# NixieClock.net
KiCad netlist of a schematic drawn in EAGLE
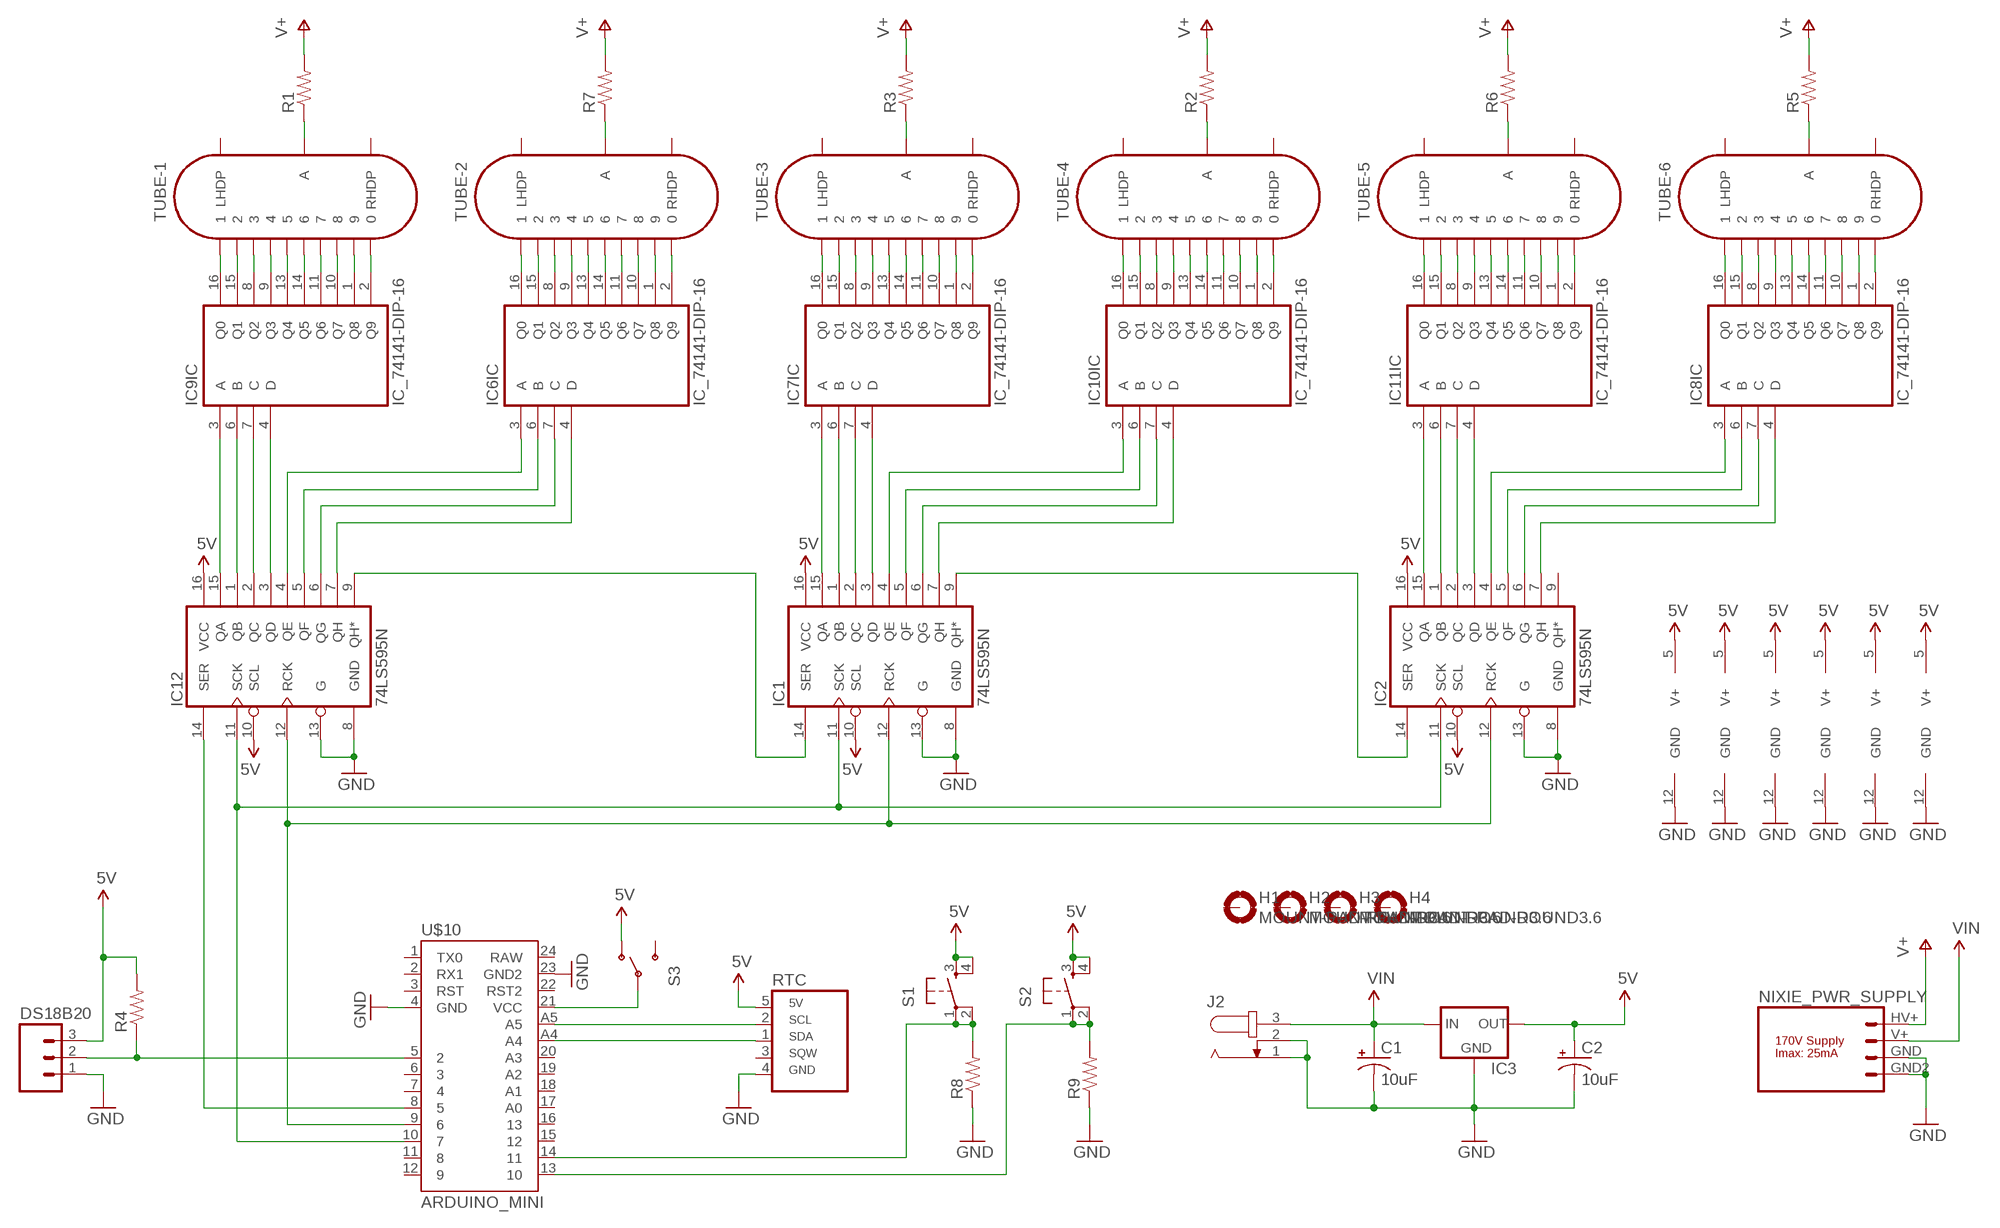
[diagram p0: schematic, sheet 1]

(export (version "E")
  (design (tool "Eeschema 10.0.6"))
  (components
    (comp (ref "C1")
      (value "10uF")
      (footprint "eagle-import:CPOL-RADIAL-10UF-25V")
      (libsource (lib "eagle-import") (part "CAP_POLPTH2"))
    )
    (comp (ref "C2")
      (value "10uF")
      (footprint "eagle-import:CPOL-RADIAL-10UF-25V")
      (libsource (lib "eagle-import") (part "CAP_POLPTH2"))
    )
    (comp (ref "DS18B20")
      (value "DS18B20DS18B20")
      (footprint "eagle-import:DS18B20")
      (libsource (lib "eagle-import") (part "DS18B20DS18B20"))
    )
    (comp (ref "H1")
      (value "MOUNT-PAD-ROUND3.6")
      (footprint "eagle-import:3,6-PAD")
      (libsource (lib "eagle-import") (part "MOUNT-PAD-ROUND3.6"))
    )
    (comp (ref "H2")
      (value "MOUNT-PAD-ROUND3.6")
      (footprint "eagle-import:3,6-PAD")
      (libsource (lib "eagle-import") (part "MOUNT-PAD-ROUND3.6"))
    )
    (comp (ref "H3")
      (value "MOUNT-PAD-ROUND3.6")
      (footprint "eagle-import:3,6-PAD")
      (libsource (lib "eagle-import") (part "MOUNT-PAD-ROUND3.6"))
    )
    (comp (ref "H4")
      (value "MOUNT-PAD-ROUND3.6")
      (footprint "eagle-import:3,6-PAD")
      (libsource (lib "eagle-import") (part "MOUNT-PAD-ROUND3.6"))
    )
    (comp (ref "IC1")
      (value "74LS595N")
      (footprint "eagle-import:DIL16")
      (libsource (lib "eagle-import") (part "74595NLS"))
    )
    (comp (ref "IC2")
      (value "74LS595N")
      (footprint "eagle-import:DIL16")
      (libsource (lib "eagle-import") (part "74595NLS"))
    )
    (comp (ref "IC3")
      (value "V_REG_78XXSIDE")
      (footprint "eagle-import:78XXL")
      (libsource (lib "eagle-import") (part "V_REG_78XXSIDE"))
    )
    (comp (ref "IC6")
      (value "IC_74141-DIP-16")
      (footprint "eagle-import:DIL16")
      (libsource (lib "eagle-import") (part "IC_74141-DIP-16"))
    )
    (comp (ref "IC7")
      (value "IC_74141-DIP-16")
      (footprint "eagle-import:DIL16")
      (libsource (lib "eagle-import") (part "IC_74141-DIP-16"))
    )
    (comp (ref "IC8")
      (value "IC_74141-DIP-16")
      (footprint "eagle-import:DIL16")
      (libsource (lib "eagle-import") (part "IC_74141-DIP-16"))
    )
    (comp (ref "IC9")
      (value "IC_74141-DIP-16")
      (footprint "eagle-import:DIL16")
      (libsource (lib "eagle-import") (part "IC_74141-DIP-16"))
    )
    (comp (ref "IC10")
      (value "IC_74141-DIP-16")
      (footprint "eagle-import:DIL16")
      (libsource (lib "eagle-import") (part "IC_74141-DIP-16"))
    )
    (comp (ref "IC11")
      (value "IC_74141-DIP-16")
      (footprint "eagle-import:DIL16")
      (libsource (lib "eagle-import") (part "IC_74141-DIP-16"))
    )
    (comp (ref "IC12")
      (value "74LS595N")
      (footprint "eagle-import:DIL16")
      (libsource (lib "eagle-import") (part "74595NLS"))
    )
    (comp (ref "J2")
      (value "JACK-PLUG0")
      (footprint "eagle-import:SPC4077")
      (libsource (lib "eagle-import") (part "JACK-PLUG0"))
    )
    (comp (ref "NIXIE_PWR_SUPPLY")
      (value "NIXIE_PWR_SUPPLYPTH")
      (footprint "eagle-import:NIXIE_PWR_SUPPLY")
      (libsource (lib "eagle-import") (part "NIXIE_PWR_SUPPLYPTH"))
    )
    (comp (ref "R1")
      (value "RESISTORPTH-1/4W")
      (footprint "eagle-import:AXIAL-0.4")
      (libsource (lib "eagle-import") (part "RESISTORPTH-1/4W"))
    )
    (comp (ref "R2")
      (value "RESISTORPTH-1/4W")
      (footprint "eagle-import:AXIAL-0.4")
      (libsource (lib "eagle-import") (part "RESISTORPTH-1/4W"))
    )
    (comp (ref "R3")
      (value "RESISTORPTH-1/4W")
      (footprint "eagle-import:AXIAL-0.4")
      (libsource (lib "eagle-import") (part "RESISTORPTH-1/4W"))
    )
    (comp (ref "R4")
      (value "RESISTORPTH-1/4W")
      (footprint "eagle-import:AXIAL-0.4")
      (libsource (lib "eagle-import") (part "SparkFun-Passives_RESISTORPTH-1/4W"))
    )
    (comp (ref "R5")
      (value "RESISTORPTH-1/4W")
      (footprint "eagle-import:AXIAL-0.4")
      (libsource (lib "eagle-import") (part "RESISTORPTH-1/4W"))
    )
    (comp (ref "R6")
      (value "RESISTORPTH-1/4W")
      (footprint "eagle-import:AXIAL-0.4")
      (libsource (lib "eagle-import") (part "RESISTORPTH-1/4W"))
    )
    (comp (ref "R7")
      (value "RESISTORPTH-1/4W")
      (footprint "eagle-import:AXIAL-0.4")
      (libsource (lib "eagle-import") (part "RESISTORPTH-1/4W"))
    )
    (comp (ref "R8")
      (value "RESISTORPTH-1/4W")
      (footprint "eagle-import:AXIAL-0.4")
      (libsource (lib "eagle-import") (part "SparkFun-Passives_RESISTORPTH-1/4W"))
    )
    (comp (ref "R9")
      (value "RESISTORPTH-1/4W")
      (footprint "eagle-import:AXIAL-0.4")
      (libsource (lib "eagle-import") (part "SparkFun-Passives_RESISTORPTH-1/4W"))
    )
    (comp (ref "RTC")
      (value "SCOTT_RTCPTH")
      (footprint "eagle-import:SCOTT_RTC")
      (libsource (lib "eagle-import") (part "SCOTT_RTCPTH"))
    )
    (comp (ref "S1")
      (value "TAC_SWITCHPTH")
      (footprint "eagle-import:TACTILE-PTH")
      (libsource (lib "eagle-import") (part "TAC_SWITCHPTH"))
    )
    (comp (ref "S2")
      (value "TAC_SWITCHPTH")
      (footprint "eagle-import:TACTILE-PTH")
      (libsource (lib "eagle-import") (part "TAC_SWITCHPTH"))
    )
    (comp (ref "S3")
      (value "SWITCH-SPDTPTH")
      (footprint "eagle-import:SWITCH-SPDT")
      (libsource (lib "eagle-import") (part "SWITCH-SPDTPTH"))
    )
    (comp (ref "TUBE-1")
      (value "IN-14")
      (footprint "eagle-import:IN-14")
      (libsource (lib "eagle-import") (part "IN-14"))
    )
    (comp (ref "TUBE-2")
      (value "IN-14")
      (footprint "eagle-import:IN-14")
      (libsource (lib "eagle-import") (part "IN-14"))
    )
    (comp (ref "TUBE-3")
      (value "IN-14")
      (footprint "eagle-import:IN-14")
      (libsource (lib "eagle-import") (part "IN-14"))
    )
    (comp (ref "TUBE-4")
      (value "IN-14")
      (footprint "eagle-import:IN-14")
      (libsource (lib "eagle-import") (part "IN-14"))
    )
    (comp (ref "TUBE-5")
      (value "IN-14")
      (footprint "eagle-import:IN-14")
      (libsource (lib "eagle-import") (part "IN-14"))
    )
    (comp (ref "TUBE-6")
      (value "IN-14")
      (footprint "eagle-import:IN-14")
      (libsource (lib "eagle-import") (part "IN-14"))
    )
    (comp (ref "U$10")
      (value "ARDUINO_MINI")
      (footprint "eagle-import:ARDUINO_MINI")
      (libsource (lib "eagle-import") (part "ARDUINO_MINI"))
    )
  )
  (nets
    (net (code "1") (name "5V") (class "Default")
      (node (ref "C2") (pin "1") (pinfunction "+_1") (pintype "passive"))
      (node (ref "DS18B20") (pin "3") (pinfunction "5V_3") (pintype "passive"))
      (node (ref "IC1") (pin "10") (pinfunction "SCL_10") (pintype "input"))
      (node (ref "IC1") (pin "16") (pinfunction "VCC_16") (pintype "power_in"))
      (node (ref "IC10") (pin "5") (pinfunction "V+_5") (pintype "power_in"))
      (node (ref "IC11") (pin "5") (pinfunction "V+_5") (pintype "power_in"))
      (node (ref "IC12") (pin "10") (pinfunction "SCL_10") (pintype "input"))
      (node (ref "IC12") (pin "16") (pinfunction "VCC_16") (pintype "power_in"))
      (node (ref "IC2") (pin "10") (pinfunction "SCL_10") (pintype "input"))
      (node (ref "IC2") (pin "16") (pinfunction "VCC_16") (pintype "power_in"))
      (node (ref "IC3") (pin "OUT") (pinfunction "OUT_OUT") (pintype "output"))
      (node (ref "IC6") (pin "5") (pinfunction "V+_5") (pintype "power_in"))
      (node (ref "IC7") (pin "5") (pinfunction "V+_5") (pintype "power_in"))
      (node (ref "IC8") (pin "5") (pinfunction "V+_5") (pintype "power_in"))
      (node (ref "IC9") (pin "5") (pinfunction "V+_5") (pintype "power_in"))
      (node (ref "R4") (pin "P$2") (pinfunction "2_P$2") (pintype "passive"))
      (node (ref "RTC") (pin "5") (pinfunction "5V_5") (pintype "passive"))
      (node (ref "S1") (pin "3") (pinfunction "3_3") (pintype "passive"))
      (node (ref "S1") (pin "4") (pinfunction "4_4") (pintype "passive"))
      (node (ref "S2") (pin "3") (pinfunction "3_3") (pintype "passive"))
      (node (ref "S2") (pin "4") (pinfunction "4_4") (pintype "passive"))
      (node (ref "S3") (pin "1") (pinfunction "O_1") (pintype "passive"))
    )
    (net (code "2") (name "GND") (class "Default")
      (node (ref "C1") (pin "2") (pinfunction "-_2") (pintype "passive"))
      (node (ref "C2") (pin "2") (pinfunction "-_2") (pintype "passive"))
      (node (ref "DS18B20") (pin "1") (pinfunction "GND_1") (pintype "passive"))
      (node (ref "IC1") (pin "13") (pinfunction "G_13") (pintype "input"))
      (node (ref "IC1") (pin "8") (pinfunction "GND_8") (pintype "power_in"))
      (node (ref "IC10") (pin "12") (pinfunction "GND_12") (pintype "power_in"))
      (node (ref "IC11") (pin "12") (pinfunction "GND_12") (pintype "power_in"))
      (node (ref "IC12") (pin "13") (pinfunction "G_13") (pintype "input"))
      (node (ref "IC12") (pin "8") (pinfunction "GND_8") (pintype "power_in"))
      (node (ref "IC2") (pin "13") (pinfunction "G_13") (pintype "input"))
      (node (ref "IC2") (pin "8") (pinfunction "GND_8") (pintype "power_in"))
      (node (ref "IC3") (pin "GND") (pinfunction "GND_GND") (pintype "input"))
      (node (ref "IC6") (pin "12") (pinfunction "GND_12") (pintype "power_in"))
      (node (ref "IC7") (pin "12") (pinfunction "GND_12") (pintype "power_in"))
      (node (ref "IC8") (pin "12") (pinfunction "GND_12") (pintype "power_in"))
      (node (ref "IC9") (pin "12") (pinfunction "GND_12") (pintype "power_in"))
      (node (ref "J2") (pin "1") (pinfunction "1_1") (pintype "passive"))
      (node (ref "J2") (pin "2") (pinfunction "2_2") (pintype "passive"))
      (node (ref "NIXIE_PWR_SUPPLY") (pin "GND") (pinfunction "4_GND") (pintype "passive"))
      (node (ref "NIXIE_PWR_SUPPLY") (pin "GND2") (pinfunction "1_GND2") (pintype "passive"))
      (node (ref "R8") (pin "P$1") (pinfunction "1_P$1") (pintype "passive"))
      (node (ref "R9") (pin "P$1") (pinfunction "1_P$1") (pintype "passive"))
      (node (ref "RTC") (pin "4") (pinfunction "GND_4") (pintype "passive"))
      (node (ref "U$10") (pin "23") (pinfunction "GND2_23") (pintype "bidirectional"))
      (node (ref "U$10") (pin "4") (pinfunction "GND_4") (pintype "bidirectional"))
    )
    (net (code "3") (name "Net-(DS18B20-DS)") (class "Default")
      (node (ref "DS18B20") (pin "2") (pinfunction "DS_2") (pintype "passive"))
      (node (ref "R4") (pin "P$1") (pinfunction "1_P$1") (pintype "passive"))
      (node (ref "U$10") (pin "5") (pinfunction "2_5") (pintype "bidirectional"))
    )
    (net (code "4") (name "Net-(IC1-QA)") (class "Default")
      (node (ref "IC1") (pin "15") (pinfunction "QA_15") (pintype "tri_state"))
      (node (ref "IC7") (pin "3") (pinfunction "A_3") (pintype "input"))
    )
    (net (code "5") (name "Net-(IC1-QB)") (class "Default")
      (node (ref "IC1") (pin "1") (pinfunction "QB_1") (pintype "tri_state"))
      (node (ref "IC7") (pin "6") (pinfunction "B_6") (pintype "input"))
    )
    (net (code "6") (name "Net-(IC1-QC)") (class "Default")
      (node (ref "IC1") (pin "2") (pinfunction "QC_2") (pintype "tri_state"))
      (node (ref "IC7") (pin "7") (pinfunction "C_7") (pintype "input"))
    )
    (net (code "7") (name "Net-(IC1-QD)") (class "Default")
      (node (ref "IC1") (pin "3") (pinfunction "QD_3") (pintype "tri_state"))
      (node (ref "IC7") (pin "4") (pinfunction "D_4") (pintype "input"))
    )
    (net (code "8") (name "Net-(IC1-QE)") (class "Default")
      (node (ref "IC1") (pin "4") (pinfunction "QE_4") (pintype "tri_state"))
      (node (ref "IC10") (pin "3") (pinfunction "A_3") (pintype "input"))
    )
    (net (code "9") (name "Net-(IC1-QF)") (class "Default")
      (node (ref "IC1") (pin "5") (pinfunction "QF_5") (pintype "tri_state"))
      (node (ref "IC10") (pin "6") (pinfunction "B_6") (pintype "input"))
    )
    (net (code "10") (name "Net-(IC1-QG)") (class "Default")
      (node (ref "IC1") (pin "6") (pinfunction "QG_6") (pintype "tri_state"))
      (node (ref "IC10") (pin "7") (pinfunction "C_7") (pintype "input"))
    )
    (net (code "11") (name "Net-(IC1-QH)") (class "Default")
      (node (ref "IC1") (pin "7") (pinfunction "QH_7") (pintype "tri_state"))
      (node (ref "IC10") (pin "4") (pinfunction "D_4") (pintype "input"))
    )
    (net (code "12") (name "Net-(IC1-QH*)") (class "Default")
      (node (ref "IC1") (pin "9") (pinfunction "QH*_9") (pintype "tri_state"))
      (node (ref "IC2") (pin "14") (pinfunction "SER_14") (pintype "input"))
    )
    (net (code "13") (name "Net-(IC1-RCK)") (class "Default")
      (node (ref "IC1") (pin "12") (pinfunction "RCK_12") (pintype "input"))
      (node (ref "IC12") (pin "12") (pinfunction "RCK_12") (pintype "input"))
      (node (ref "IC2") (pin "12") (pinfunction "RCK_12") (pintype "input"))
      (node (ref "U$10") (pin "9") (pinfunction "6_9") (pintype "bidirectional"))
    )
    (net (code "14") (name "Net-(IC1-SCK)") (class "Default")
      (node (ref "IC1") (pin "11") (pinfunction "SCK_11") (pintype "input"))
      (node (ref "IC12") (pin "11") (pinfunction "SCK_11") (pintype "input"))
      (node (ref "IC2") (pin "11") (pinfunction "SCK_11") (pintype "input"))
      (node (ref "U$10") (pin "10") (pinfunction "7_10") (pintype "bidirectional"))
    )
    (net (code "15") (name "Net-(IC1-SER)") (class "Default")
      (node (ref "IC1") (pin "14") (pinfunction "SER_14") (pintype "input"))
      (node (ref "IC12") (pin "9") (pinfunction "QH*_9") (pintype "tri_state"))
    )
    (net (code "16") (name "Net-(IC2-QE)") (class "Default")
      (node (ref "IC2") (pin "4") (pinfunction "QE_4") (pintype "tri_state"))
      (node (ref "IC8") (pin "3") (pinfunction "A_3") (pintype "input"))
    )
    (net (code "17") (name "Net-(IC2-QF)") (class "Default")
      (node (ref "IC2") (pin "5") (pinfunction "QF_5") (pintype "tri_state"))
      (node (ref "IC8") (pin "6") (pinfunction "B_6") (pintype "input"))
    )
    (net (code "18") (name "Net-(IC2-QG)") (class "Default")
      (node (ref "IC2") (pin "6") (pinfunction "QG_6") (pintype "tri_state"))
      (node (ref "IC8") (pin "7") (pinfunction "C_7") (pintype "input"))
    )
    (net (code "19") (name "Net-(IC2-QH)") (class "Default")
      (node (ref "IC2") (pin "7") (pinfunction "QH_7") (pintype "tri_state"))
      (node (ref "IC8") (pin "4") (pinfunction "D_4") (pintype "input"))
    )
    (net (code "20") (name "Net-(IC6A-Q0)") (class "Default")
      (node (ref "IC6") (pin "16") (pinfunction "Q0_16") (pintype "output"))
      (node (ref "TUBE-2") (pin "1") (pinfunction "1_1") (pintype "bidirectional"))
    )
    (net (code "21") (name "Net-(IC6A-Q1)") (class "Default")
      (node (ref "IC6") (pin "15") (pinfunction "Q1_15") (pintype "output"))
      (node (ref "TUBE-2") (pin "2") (pinfunction "2_2") (pintype "bidirectional"))
    )
    (net (code "22") (name "Net-(IC6A-Q2)") (class "Default")
      (node (ref "IC6") (pin "8") (pinfunction "Q2_8") (pintype "output"))
      (node (ref "TUBE-2") (pin "3") (pinfunction "3_3") (pintype "bidirectional"))
    )
    (net (code "23") (name "Net-(IC6A-Q3)") (class "Default")
      (node (ref "IC6") (pin "9") (pinfunction "Q3_9") (pintype "output"))
      (node (ref "TUBE-2") (pin "4") (pinfunction "4_4") (pintype "bidirectional"))
    )
    (net (code "24") (name "Net-(IC6A-Q4)") (class "Default")
      (node (ref "IC6") (pin "13") (pinfunction "Q4_13") (pintype "output"))
      (node (ref "TUBE-2") (pin "5") (pinfunction "5_5") (pintype "bidirectional"))
    )
    (net (code "25") (name "Net-(IC6A-Q5)") (class "Default")
      (node (ref "IC6") (pin "14") (pinfunction "Q5_14") (pintype "output"))
      (node (ref "TUBE-2") (pin "6") (pinfunction "6_6") (pintype "bidirectional"))
    )
    (net (code "26") (name "Net-(IC6A-Q6)") (class "Default")
      (node (ref "IC6") (pin "11") (pinfunction "Q6_11") (pintype "output"))
      (node (ref "TUBE-2") (pin "7") (pinfunction "7_7") (pintype "bidirectional"))
    )
    (net (code "27") (name "Net-(IC6A-Q7)") (class "Default")
      (node (ref "IC6") (pin "10") (pinfunction "Q7_10") (pintype "output"))
      (node (ref "TUBE-2") (pin "8") (pinfunction "8_8") (pintype "bidirectional"))
    )
    (net (code "28") (name "Net-(IC6A-Q8)") (class "Default")
      (node (ref "IC6") (pin "1") (pinfunction "Q8_1") (pintype "output"))
      (node (ref "TUBE-2") (pin "9") (pinfunction "9_9") (pintype "bidirectional"))
    )
    (net (code "29") (name "Net-(IC6A-Q9)") (class "Default")
      (node (ref "IC6") (pin "2") (pinfunction "Q9_2") (pintype "output"))
      (node (ref "TUBE-2") (pin "0") (pinfunction "0_0") (pintype "bidirectional"))
    )
    (net (code "30") (name "Net-(IC7A-Q0)") (class "Default")
      (node (ref "IC7") (pin "16") (pinfunction "Q0_16") (pintype "output"))
      (node (ref "TUBE-3") (pin "1") (pinfunction "1_1") (pintype "bidirectional"))
    )
    (net (code "31") (name "Net-(IC7A-Q1)") (class "Default")
      (node (ref "IC7") (pin "15") (pinfunction "Q1_15") (pintype "output"))
      (node (ref "TUBE-3") (pin "2") (pinfunction "2_2") (pintype "bidirectional"))
    )
    (net (code "32") (name "Net-(IC7A-Q2)") (class "Default")
      (node (ref "IC7") (pin "8") (pinfunction "Q2_8") (pintype "output"))
      (node (ref "TUBE-3") (pin "3") (pinfunction "3_3") (pintype "bidirectional"))
    )
    (net (code "33") (name "Net-(IC7A-Q3)") (class "Default")
      (node (ref "IC7") (pin "9") (pinfunction "Q3_9") (pintype "output"))
      (node (ref "TUBE-3") (pin "4") (pinfunction "4_4") (pintype "bidirectional"))
    )
    (net (code "34") (name "Net-(IC7A-Q4)") (class "Default")
      (node (ref "IC7") (pin "13") (pinfunction "Q4_13") (pintype "output"))
      (node (ref "TUBE-3") (pin "5") (pinfunction "5_5") (pintype "bidirectional"))
    )
    (net (code "35") (name "Net-(IC7A-Q5)") (class "Default")
      (node (ref "IC7") (pin "14") (pinfunction "Q5_14") (pintype "output"))
      (node (ref "TUBE-3") (pin "6") (pinfunction "6_6") (pintype "bidirectional"))
    )
    (net (code "36") (name "Net-(IC7A-Q6)") (class "Default")
      (node (ref "IC7") (pin "11") (pinfunction "Q6_11") (pintype "output"))
      (node (ref "TUBE-3") (pin "7") (pinfunction "7_7") (pintype "bidirectional"))
    )
    (net (code "37") (name "Net-(IC7A-Q7)") (class "Default")
      (node (ref "IC7") (pin "10") (pinfunction "Q7_10") (pintype "output"))
      (node (ref "TUBE-3") (pin "8") (pinfunction "8_8") (pintype "bidirectional"))
    )
    (net (code "38") (name "Net-(IC7A-Q8)") (class "Default")
      (node (ref "IC7") (pin "1") (pinfunction "Q8_1") (pintype "output"))
      (node (ref "TUBE-3") (pin "9") (pinfunction "9_9") (pintype "bidirectional"))
    )
    (net (code "39") (name "Net-(IC7A-Q9)") (class "Default")
      (node (ref "IC7") (pin "2") (pinfunction "Q9_2") (pintype "output"))
      (node (ref "TUBE-3") (pin "0") (pinfunction "0_0") (pintype "bidirectional"))
    )
    (net (code "40") (name "Net-(IC8A-Q0)") (class "Default")
      (node (ref "IC8") (pin "16") (pinfunction "Q0_16") (pintype "output"))
      (node (ref "TUBE-6") (pin "1") (pinfunction "1_1") (pintype "bidirectional"))
    )
    (net (code "41") (name "Net-(IC8A-Q1)") (class "Default")
      (node (ref "IC8") (pin "15") (pinfunction "Q1_15") (pintype "output"))
      (node (ref "TUBE-6") (pin "2") (pinfunction "2_2") (pintype "bidirectional"))
    )
    (net (code "42") (name "Net-(IC8A-Q2)") (class "Default")
      (node (ref "IC8") (pin "8") (pinfunction "Q2_8") (pintype "output"))
      (node (ref "TUBE-6") (pin "3") (pinfunction "3_3") (pintype "bidirectional"))
    )
    (net (code "43") (name "Net-(IC8A-Q3)") (class "Default")
      (node (ref "IC8") (pin "9") (pinfunction "Q3_9") (pintype "output"))
      (node (ref "TUBE-6") (pin "4") (pinfunction "4_4") (pintype "bidirectional"))
    )
    (net (code "44") (name "Net-(IC8A-Q4)") (class "Default")
      (node (ref "IC8") (pin "13") (pinfunction "Q4_13") (pintype "output"))
      (node (ref "TUBE-6") (pin "5") (pinfunction "5_5") (pintype "bidirectional"))
    )
    (net (code "45") (name "Net-(IC8A-Q5)") (class "Default")
      (node (ref "IC8") (pin "14") (pinfunction "Q5_14") (pintype "output"))
      (node (ref "TUBE-6") (pin "6") (pinfunction "6_6") (pintype "bidirectional"))
    )
    (net (code "46") (name "Net-(IC8A-Q6)") (class "Default")
      (node (ref "IC8") (pin "11") (pinfunction "Q6_11") (pintype "output"))
      (node (ref "TUBE-6") (pin "7") (pinfunction "7_7") (pintype "bidirectional"))
    )
    (net (code "47") (name "Net-(IC8A-Q7)") (class "Default")
      (node (ref "IC8") (pin "10") (pinfunction "Q7_10") (pintype "output"))
      (node (ref "TUBE-6") (pin "8") (pinfunction "8_8") (pintype "bidirectional"))
    )
    (net (code "48") (name "Net-(IC8A-Q8)") (class "Default")
      (node (ref "IC8") (pin "1") (pinfunction "Q8_1") (pintype "output"))
      (node (ref "TUBE-6") (pin "9") (pinfunction "9_9") (pintype "bidirectional"))
    )
    (net (code "49") (name "Net-(IC8A-Q9)") (class "Default")
      (node (ref "IC8") (pin "2") (pinfunction "Q9_2") (pintype "output"))
      (node (ref "TUBE-6") (pin "0") (pinfunction "0_0") (pintype "bidirectional"))
    )
    (net (code "50") (name "Net-(IC9A-Q0)") (class "Default")
      (node (ref "IC9") (pin "16") (pinfunction "Q0_16") (pintype "output"))
      (node (ref "TUBE-1") (pin "1") (pinfunction "1_1") (pintype "bidirectional"))
    )
    (net (code "51") (name "Net-(IC9A-Q1)") (class "Default")
      (node (ref "IC9") (pin "15") (pinfunction "Q1_15") (pintype "output"))
      (node (ref "TUBE-1") (pin "2") (pinfunction "2_2") (pintype "bidirectional"))
    )
    (net (code "52") (name "Net-(IC9A-Q2)") (class "Default")
      (node (ref "IC9") (pin "8") (pinfunction "Q2_8") (pintype "output"))
      (node (ref "TUBE-1") (pin "3") (pinfunction "3_3") (pintype "bidirectional"))
    )
    (net (code "53") (name "Net-(IC9A-Q3)") (class "Default")
      (node (ref "IC9") (pin "9") (pinfunction "Q3_9") (pintype "output"))
      (node (ref "TUBE-1") (pin "4") (pinfunction "4_4") (pintype "bidirectional"))
    )
    (net (code "54") (name "Net-(IC9A-Q4)") (class "Default")
      (node (ref "IC9") (pin "13") (pinfunction "Q4_13") (pintype "output"))
      (node (ref "TUBE-1") (pin "5") (pinfunction "5_5") (pintype "bidirectional"))
    )
    (net (code "55") (name "Net-(IC9A-Q5)") (class "Default")
      (node (ref "IC9") (pin "14") (pinfunction "Q5_14") (pintype "output"))
      (node (ref "TUBE-1") (pin "6") (pinfunction "6_6") (pintype "bidirectional"))
    )
    (net (code "56") (name "Net-(IC9A-Q6)") (class "Default")
      (node (ref "IC9") (pin "11") (pinfunction "Q6_11") (pintype "output"))
      (node (ref "TUBE-1") (pin "7") (pinfunction "7_7") (pintype "bidirectional"))
    )
    (net (code "57") (name "Net-(IC9A-Q7)") (class "Default")
      (node (ref "IC9") (pin "10") (pinfunction "Q7_10") (pintype "output"))
      (node (ref "TUBE-1") (pin "8") (pinfunction "8_8") (pintype "bidirectional"))
    )
    (net (code "58") (name "Net-(IC9A-Q8)") (class "Default")
      (node (ref "IC9") (pin "1") (pinfunction "Q8_1") (pintype "output"))
      (node (ref "TUBE-1") (pin "9") (pinfunction "9_9") (pintype "bidirectional"))
    )
    (net (code "59") (name "Net-(IC9A-Q9)") (class "Default")
      (node (ref "IC9") (pin "2") (pinfunction "Q9_2") (pintype "output"))
      (node (ref "TUBE-1") (pin "0") (pinfunction "0_0") (pintype "bidirectional"))
    )
    (net (code "60") (name "Net-(IC10A-Q0)") (class "Default")
      (node (ref "IC10") (pin "16") (pinfunction "Q0_16") (pintype "output"))
      (node (ref "TUBE-4") (pin "1") (pinfunction "1_1") (pintype "bidirectional"))
    )
    (net (code "61") (name "Net-(IC10A-Q1)") (class "Default")
      (node (ref "IC10") (pin "15") (pinfunction "Q1_15") (pintype "output"))
      (node (ref "TUBE-4") (pin "2") (pinfunction "2_2") (pintype "bidirectional"))
    )
    (net (code "62") (name "Net-(IC10A-Q2)") (class "Default")
      (node (ref "IC10") (pin "8") (pinfunction "Q2_8") (pintype "output"))
      (node (ref "TUBE-4") (pin "3") (pinfunction "3_3") (pintype "bidirectional"))
    )
    (net (code "63") (name "Net-(IC10A-Q3)") (class "Default")
      (node (ref "IC10") (pin "9") (pinfunction "Q3_9") (pintype "output"))
      (node (ref "TUBE-4") (pin "4") (pinfunction "4_4") (pintype "bidirectional"))
    )
    (net (code "64") (name "Net-(IC10A-Q4)") (class "Default")
      (node (ref "IC10") (pin "13") (pinfunction "Q4_13") (pintype "output"))
      (node (ref "TUBE-4") (pin "5") (pinfunction "5_5") (pintype "bidirectional"))
    )
    (net (code "65") (name "Net-(IC10A-Q5)") (class "Default")
      (node (ref "IC10") (pin "14") (pinfunction "Q5_14") (pintype "output"))
      (node (ref "TUBE-4") (pin "6") (pinfunction "6_6") (pintype "bidirectional"))
    )
    (net (code "66") (name "Net-(IC10A-Q6)") (class "Default")
      (node (ref "IC10") (pin "11") (pinfunction "Q6_11") (pintype "output"))
      (node (ref "TUBE-4") (pin "7") (pinfunction "7_7") (pintype "bidirectional"))
    )
    (net (code "67") (name "Net-(IC10A-Q7)") (class "Default")
      (node (ref "IC10") (pin "10") (pinfunction "Q7_10") (pintype "output"))
      (node (ref "TUBE-4") (pin "8") (pinfunction "8_8") (pintype "bidirectional"))
    )
    (net (code "68") (name "Net-(IC10A-Q8)") (class "Default")
      (node (ref "IC10") (pin "1") (pinfunction "Q8_1") (pintype "output"))
      (node (ref "TUBE-4") (pin "9") (pinfunction "9_9") (pintype "bidirectional"))
    )
    (net (code "69") (name "Net-(IC10A-Q9)") (class "Default")
      (node (ref "IC10") (pin "2") (pinfunction "Q9_2") (pintype "output"))
      (node (ref "TUBE-4") (pin "0") (pinfunction "0_0") (pintype "bidirectional"))
    )
    (net (code "70") (name "Net-(IC11A-A)") (class "Default")
      (node (ref "IC11") (pin "3") (pinfunction "A_3") (pintype "input"))
      (node (ref "IC2") (pin "15") (pinfunction "QA_15") (pintype "tri_state"))
    )
    (net (code "71") (name "Net-(IC11A-B)") (class "Default")
      (node (ref "IC11") (pin "6") (pinfunction "B_6") (pintype "input"))
      (node (ref "IC2") (pin "1") (pinfunction "QB_1") (pintype "tri_state"))
    )
    (net (code "72") (name "Net-(IC11A-C)") (class "Default")
      (node (ref "IC11") (pin "7") (pinfunction "C_7") (pintype "input"))
      (node (ref "IC2") (pin "2") (pinfunction "QC_2") (pintype "tri_state"))
    )
    (net (code "73") (name "Net-(IC11A-D)") (class "Default")
      (node (ref "IC11") (pin "4") (pinfunction "D_4") (pintype "input"))
      (node (ref "IC2") (pin "3") (pinfunction "QD_3") (pintype "tri_state"))
    )
    (net (code "74") (name "Net-(IC11A-Q0)") (class "Default")
      (node (ref "IC11") (pin "16") (pinfunction "Q0_16") (pintype "output"))
      (node (ref "TUBE-5") (pin "1") (pinfunction "1_1") (pintype "bidirectional"))
    )
    (net (code "75") (name "Net-(IC11A-Q1)") (class "Default")
      (node (ref "IC11") (pin "15") (pinfunction "Q1_15") (pintype "output"))
      (node (ref "TUBE-5") (pin "2") (pinfunction "2_2") (pintype "bidirectional"))
    )
    (net (code "76") (name "Net-(IC11A-Q2)") (class "Default")
      (node (ref "IC11") (pin "8") (pinfunction "Q2_8") (pintype "output"))
      (node (ref "TUBE-5") (pin "3") (pinfunction "3_3") (pintype "bidirectional"))
    )
    (net (code "77") (name "Net-(IC11A-Q3)") (class "Default")
      (node (ref "IC11") (pin "9") (pinfunction "Q3_9") (pintype "output"))
      (node (ref "TUBE-5") (pin "4") (pinfunction "4_4") (pintype "bidirectional"))
    )
    (net (code "78") (name "Net-(IC11A-Q4)") (class "Default")
      (node (ref "IC11") (pin "13") (pinfunction "Q4_13") (pintype "output"))
      (node (ref "TUBE-5") (pin "5") (pinfunction "5_5") (pintype "bidirectional"))
    )
    (net (code "79") (name "Net-(IC11A-Q5)") (class "Default")
      (node (ref "IC11") (pin "14") (pinfunction "Q5_14") (pintype "output"))
      (node (ref "TUBE-5") (pin "6") (pinfunction "6_6") (pintype "bidirectional"))
    )
    (net (code "80") (name "Net-(IC11A-Q6)") (class "Default")
      (node (ref "IC11") (pin "11") (pinfunction "Q6_11") (pintype "output"))
      (node (ref "TUBE-5") (pin "7") (pinfunction "7_7") (pintype "bidirectional"))
    )
    (net (code "81") (name "Net-(IC11A-Q7)") (class "Default")
      (node (ref "IC11") (pin "10") (pinfunction "Q7_10") (pintype "output"))
      (node (ref "TUBE-5") (pin "8") (pinfunction "8_8") (pintype "bidirectional"))
    )
    (net (code "82") (name "Net-(IC11A-Q8)") (class "Default")
      (node (ref "IC11") (pin "1") (pinfunction "Q8_1") (pintype "output"))
      (node (ref "TUBE-5") (pin "9") (pinfunction "9_9") (pintype "bidirectional"))
    )
    (net (code "83") (name "Net-(IC11A-Q9)") (class "Default")
      (node (ref "IC11") (pin "2") (pinfunction "Q9_2") (pintype "output"))
      (node (ref "TUBE-5") (pin "0") (pinfunction "0_0") (pintype "bidirectional"))
    )
    (net (code "84") (name "Net-(IC12-QA)") (class "Default")
      (node (ref "IC12") (pin "15") (pinfunction "QA_15") (pintype "tri_state"))
      (node (ref "IC9") (pin "3") (pinfunction "A_3") (pintype "input"))
    )
    (net (code "85") (name "Net-(IC12-QB)") (class "Default")
      (node (ref "IC12") (pin "1") (pinfunction "QB_1") (pintype "tri_state"))
      (node (ref "IC9") (pin "6") (pinfunction "B_6") (pintype "input"))
    )
    (net (code "86") (name "Net-(IC12-QC)") (class "Default")
      (node (ref "IC12") (pin "2") (pinfunction "QC_2") (pintype "tri_state"))
      (node (ref "IC9") (pin "7") (pinfunction "C_7") (pintype "input"))
    )
    (net (code "87") (name "Net-(IC12-QD)") (class "Default")
      (node (ref "IC12") (pin "3") (pinfunction "QD_3") (pintype "tri_state"))
      (node (ref "IC9") (pin "4") (pinfunction "D_4") (pintype "input"))
    )
    (net (code "88") (name "Net-(IC12-QE)") (class "Default")
      (node (ref "IC12") (pin "4") (pinfunction "QE_4") (pintype "tri_state"))
      (node (ref "IC6") (pin "3") (pinfunction "A_3") (pintype "input"))
    )
    (net (code "89") (name "Net-(IC12-QF)") (class "Default")
      (node (ref "IC12") (pin "5") (pinfunction "QF_5") (pintype "tri_state"))
      (node (ref "IC6") (pin "6") (pinfunction "B_6") (pintype "input"))
    )
    (net (code "90") (name "Net-(IC12-QG)") (class "Default")
      (node (ref "IC12") (pin "6") (pinfunction "QG_6") (pintype "tri_state"))
      (node (ref "IC6") (pin "7") (pinfunction "C_7") (pintype "input"))
    )
    (net (code "91") (name "Net-(IC12-QH)") (class "Default")
      (node (ref "IC12") (pin "7") (pinfunction "QH_7") (pintype "tri_state"))
      (node (ref "IC6") (pin "4") (pinfunction "D_4") (pintype "input"))
    )
    (net (code "92") (name "Net-(IC12-SER)") (class "Default")
      (node (ref "IC12") (pin "14") (pinfunction "SER_14") (pintype "input"))
      (node (ref "U$10") (pin "8") (pinfunction "5_8") (pintype "bidirectional"))
    )
    (net (code "93") (name "Net-(R1-1)") (class "Default")
      (node (ref "R1") (pin "P$1") (pinfunction "1_P$1") (pintype "passive"))
      (node (ref "TUBE-1") (pin "A") (pinfunction "A_A") (pintype "bidirectional"))
    )
    (net (code "94") (name "Net-(R2-1)") (class "Default")
      (node (ref "R2") (pin "P$1") (pinfunction "1_P$1") (pintype "passive"))
      (node (ref "TUBE-4") (pin "A") (pinfunction "A_A") (pintype "bidirectional"))
    )
    (net (code "95") (name "Net-(R3-1)") (class "Default")
      (node (ref "R3") (pin "P$1") (pinfunction "1_P$1") (pintype "passive"))
      (node (ref "TUBE-3") (pin "A") (pinfunction "A_A") (pintype "bidirectional"))
    )
    (net (code "96") (name "Net-(R5-1)") (class "Default")
      (node (ref "R5") (pin "P$1") (pinfunction "1_P$1") (pintype "passive"))
      (node (ref "TUBE-6") (pin "A") (pinfunction "A_A") (pintype "bidirectional"))
    )
    (net (code "97") (name "Net-(R6-1)") (class "Default")
      (node (ref "R6") (pin "P$1") (pinfunction "1_P$1") (pintype "passive"))
      (node (ref "TUBE-5") (pin "A") (pinfunction "A_A") (pintype "bidirectional"))
    )
    (net (code "98") (name "Net-(R7-1)") (class "Default")
      (node (ref "R7") (pin "P$1") (pinfunction "1_P$1") (pintype "passive"))
      (node (ref "TUBE-2") (pin "A") (pinfunction "A_A") (pintype "bidirectional"))
    )
    (net (code "99") (name "Net-(R8-2)") (class "Default")
      (node (ref "R8") (pin "P$2") (pinfunction "2_P$2") (pintype "passive"))
      (node (ref "S1") (pin "1") (pinfunction "1_1") (pintype "passive"))
      (node (ref "S1") (pin "2") (pinfunction "2_2") (pintype "passive"))
      (node (ref "U$10") (pin "14") (pinfunction "11_14") (pintype "bidirectional"))
    )
    (net (code "100") (name "Net-(R9-2)") (class "Default")
      (node (ref "R9") (pin "P$2") (pinfunction "2_P$2") (pintype "passive"))
      (node (ref "S2") (pin "1") (pinfunction "1_1") (pintype "passive"))
      (node (ref "S2") (pin "2") (pinfunction "2_2") (pintype "passive"))
      (node (ref "U$10") (pin "13") (pinfunction "10_13") (pintype "bidirectional"))
    )
    (net (code "101") (name "Net-(RTC-SCL)") (class "Default")
      (node (ref "RTC") (pin "2") (pinfunction "SCL_2") (pintype "passive"))
      (node (ref "U$10") (pin "A5") (pinfunction "A5_A5") (pintype "bidirectional"))
    )
    (net (code "102") (name "Net-(RTC-SDA)") (class "Default")
      (node (ref "RTC") (pin "1") (pinfunction "SDA_1") (pintype "passive"))
      (node (ref "U$10") (pin "A4") (pinfunction "A4_A4") (pintype "bidirectional"))
    )
    (net (code "103") (name "Net-(S3-P)") (class "Default")
      (node (ref "S3") (pin "2") (pinfunction "P_2") (pintype "passive"))
      (node (ref "U$10") (pin "21") (pinfunction "VCC_21") (pintype "bidirectional"))
    )
    (net (code "104") (name "V+") (class "Default")
      (node (ref "NIXIE_PWR_SUPPLY") (pin "HV+") (pinfunction "3_HV+") (pintype "passive"))
      (node (ref "R1") (pin "P$2") (pinfunction "2_P$2") (pintype "passive"))
      (node (ref "R2") (pin "P$2") (pinfunction "2_P$2") (pintype "passive"))
      (node (ref "R3") (pin "P$2") (pinfunction "2_P$2") (pintype "passive"))
      (node (ref "R5") (pin "P$2") (pinfunction "2_P$2") (pintype "passive"))
      (node (ref "R6") (pin "P$2") (pinfunction "2_P$2") (pintype "passive"))
      (node (ref "R7") (pin "P$2") (pinfunction "2_P$2") (pintype "passive"))
    )
    (net (code "105") (name "VIN") (class "Default")
      (node (ref "C1") (pin "1") (pinfunction "+_1") (pintype "passive"))
      (node (ref "IC3") (pin "IN") (pinfunction "IN_IN") (pintype "input"))
      (node (ref "J2") (pin "3") (pinfunction "3_3") (pintype "passive"))
      (node (ref "NIXIE_PWR_SUPPLY") (pin "V+") (pinfunction "2_V+") (pintype "passive"))
    )
    (net (code "106") (name "unconnected-(H1-MOUNT-PadB3,6)") (class "Default")
      (node (ref "H1") (pin "B3,6") (pinfunction "MOUNT_B3,6") (pintype "passive"))
    )
    (net (code "107") (name "unconnected-(H2-MOUNT-PadB3,6)") (class "Default")
      (node (ref "H2") (pin "B3,6") (pinfunction "MOUNT_B3,6") (pintype "passive"))
    )
    (net (code "108") (name "unconnected-(H3-MOUNT-PadB3,6)") (class "Default")
      (node (ref "H3") (pin "B3,6") (pinfunction "MOUNT_B3,6") (pintype "passive"))
    )
    (net (code "109") (name "unconnected-(H4-MOUNT-PadB3,6)") (class "Default")
      (node (ref "H4") (pin "B3,6") (pinfunction "MOUNT_B3,6") (pintype "passive"))
    )
    (net (code "110") (name "unconnected-(IC2-QH*-Pad9)") (class "Default")
      (node (ref "IC2") (pin "9") (pinfunction "QH*_9") (pintype "tri_state"))
    )
    (net (code "111") (name "unconnected-(RTC-SQW-Pad3)") (class "Default")
      (node (ref "RTC") (pin "3") (pinfunction "SQW_3") (pintype "passive"))
    )
    (net (code "112") (name "unconnected-(S3-S-Pad3)") (class "Default")
      (node (ref "S3") (pin "3") (pinfunction "S_3") (pintype "passive"))
    )
    (net (code "113") (name "unconnected-(TUBE-1-PadLHDP)") (class "Default")
      (node (ref "TUBE-1") (pin "LHDP") (pinfunction "LHDP_LHDP") (pintype "bidirectional"))
    )
    (net (code "114") (name "unconnected-(TUBE-1-PadRHDP)") (class "Default")
      (node (ref "TUBE-1") (pin "RHDP") (pinfunction "RHDP_RHDP") (pintype "bidirectional"))
    )
    (net (code "115") (name "unconnected-(TUBE-2-PadLHDP)") (class "Default")
      (node (ref "TUBE-2") (pin "LHDP") (pinfunction "LHDP_LHDP") (pintype "bidirectional"))
    )
    (net (code "116") (name "unconnected-(TUBE-2-PadRHDP)") (class "Default")
      (node (ref "TUBE-2") (pin "RHDP") (pinfunction "RHDP_RHDP") (pintype "bidirectional"))
    )
    (net (code "117") (name "unconnected-(TUBE-3-PadLHDP)") (class "Default")
      (node (ref "TUBE-3") (pin "LHDP") (pinfunction "LHDP_LHDP") (pintype "bidirectional"))
    )
    (net (code "118") (name "unconnected-(TUBE-3-PadRHDP)") (class "Default")
      (node (ref "TUBE-3") (pin "RHDP") (pinfunction "RHDP_RHDP") (pintype "bidirectional"))
    )
    (net (code "119") (name "unconnected-(TUBE-4-PadLHDP)") (class "Default")
      (node (ref "TUBE-4") (pin "LHDP") (pinfunction "LHDP_LHDP") (pintype "bidirectional"))
    )
    (net (code "120") (name "unconnected-(TUBE-4-PadRHDP)") (class "Default")
      (node (ref "TUBE-4") (pin "RHDP") (pinfunction "RHDP_RHDP") (pintype "bidirectional"))
    )
    (net (code "121") (name "unconnected-(TUBE-5-PadLHDP)") (class "Default")
      (node (ref "TUBE-5") (pin "LHDP") (pinfunction "LHDP_LHDP") (pintype "bidirectional"))
    )
    (net (code "122") (name "unconnected-(TUBE-5-PadRHDP)") (class "Default")
      (node (ref "TUBE-5") (pin "RHDP") (pinfunction "RHDP_RHDP") (pintype "bidirectional"))
    )
    (net (code "123") (name "unconnected-(TUBE-6-PadLHDP)") (class "Default")
      (node (ref "TUBE-6") (pin "LHDP") (pinfunction "LHDP_LHDP") (pintype "bidirectional"))
    )
    (net (code "124") (name "unconnected-(TUBE-6-PadRHDP)") (class "Default")
      (node (ref "TUBE-6") (pin "RHDP") (pinfunction "RHDP_RHDP") (pintype "bidirectional"))
    )
    (net (code "125") (name "unconnected-(U$10-3-Pad6)") (class "Default")
      (node (ref "U$10") (pin "6") (pinfunction "3_6") (pintype "bidirectional"))
    )
    (net (code "126") (name "unconnected-(U$10-4-Pad7)") (class "Default")
      (node (ref "U$10") (pin "7") (pinfunction "4_7") (pintype "bidirectional"))
    )
    (net (code "127") (name "unconnected-(U$10-8-Pad11)") (class "Default")
      (node (ref "U$10") (pin "11") (pinfunction "8_11") (pintype "bidirectional"))
    )
    (net (code "128") (name "unconnected-(U$10-9-Pad12)") (class "Default")
      (node (ref "U$10") (pin "12") (pinfunction "9_12") (pintype "bidirectional"))
    )
    (net (code "129") (name "unconnected-(U$10-12-Pad15)") (class "Default")
      (node (ref "U$10") (pin "15") (pinfunction "12_15") (pintype "bidirectional"))
    )
    (net (code "130") (name "unconnected-(U$10-13-Pad16)") (class "Default")
      (node (ref "U$10") (pin "16") (pinfunction "13_16") (pintype "bidirectional"))
    )
    (net (code "131") (name "unconnected-(U$10-A0-Pad17)") (class "Default")
      (node (ref "U$10") (pin "17") (pinfunction "A0_17") (pintype "bidirectional"))
    )
    (net (code "132") (name "unconnected-(U$10-A1-Pad18)") (class "Default")
      (node (ref "U$10") (pin "18") (pinfunction "A1_18") (pintype "bidirectional"))
    )
    (net (code "133") (name "unconnected-(U$10-A2-Pad19)") (class "Default")
      (node (ref "U$10") (pin "19") (pinfunction "A2_19") (pintype "bidirectional"))
    )
    (net (code "134") (name "unconnected-(U$10-A3-Pad20)") (class "Default")
      (node (ref "U$10") (pin "20") (pinfunction "A3_20") (pintype "bidirectional"))
    )
    (net (code "135") (name "unconnected-(U$10-RAW-Pad24)") (class "Default")
      (node (ref "U$10") (pin "24") (pinfunction "RAW_24") (pintype "bidirectional"))
    )
    (net (code "136") (name "unconnected-(U$10-RST-Pad3)") (class "Default")
      (node (ref "U$10") (pin "3") (pinfunction "RST_3") (pintype "bidirectional"))
    )
    (net (code "137") (name "unconnected-(U$10-RST2-Pad22)") (class "Default")
      (node (ref "U$10") (pin "22") (pinfunction "RST2_22") (pintype "bidirectional"))
    )
    (net (code "138") (name "unconnected-(U$10-RX1-Pad2)") (class "Default")
      (node (ref "U$10") (pin "2") (pinfunction "RX1_2") (pintype "bidirectional"))
    )
    (net (code "139") (name "unconnected-(U$10-TX0-Pad1)") (class "Default")
      (node (ref "U$10") (pin "1") (pinfunction "TX0_1") (pintype "bidirectional"))
    )
  )
)
